# IMU_Schematics.net
KiCad netlist of a schematic drawn in Altium Designer
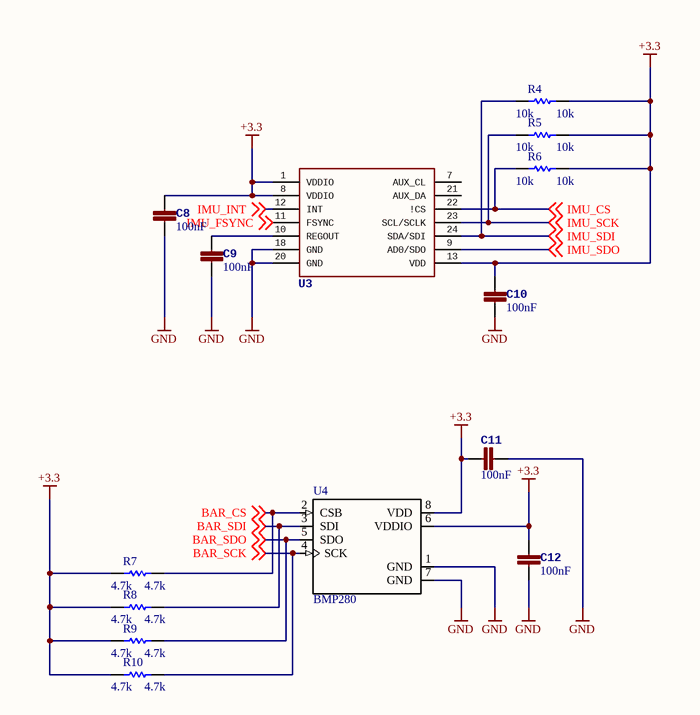
[diagram p0: IMU_Schematics.SchDoc]

(export (version "E")
  (design (tool "Eeschema 10.0.6"))
  (components
    (comp (ref "C8")
      (value "100nF")
      (footprint "_0603")
      (fields (field (name "Comment") "Cap"))
      (libsource (lib "Passives_Integrated_Library") (part "Cap_1"))
    )
    (comp (ref "C9")
      (value "100nF")
      (footprint "_0603")
      (fields (field (name "Comment") "Cap"))
      (libsource (lib "Passives_Integrated_Library") (part "Cap_1"))
    )
    (comp (ref "C10")
      (value "100nF")
      (footprint "_0603")
      (fields (field (name "Comment") "Cap"))
      (libsource (lib "Passives_Integrated_Library") (part "Cap_1"))
    )
    (comp (ref "C11")
      (value "100nF")
      (footprint "_0603")
      (fields (field (name "Comment") "Cap"))
      (libsource (lib "") (part "Cap_1_1"))
    )
    (comp (ref "C12")
      (value "100nF")
      (footprint "_0603")
      (fields (field (name "Comment") "Cap"))
      (libsource (lib "") (part "Cap_1_2"))
    )
    (comp (ref "R4")
      (value "10k")
      (footprint "RES0603")
      (description "TOTAL SMD RESISTOR PACK")
      (fields (field (name "ALTIUM_VALUE") "10k") (field (name "DESIGNER") "Abbas Basereh"))
      (libsource (lib "Passives_Integrated_Library") (part "RES SMD PACKAGE"))
    )
    (comp (ref "R5")
      (value "10k")
      (footprint "RES0603")
      (description "TOTAL SMD RESISTOR PACK")
      (fields (field (name "ALTIUM_VALUE") "10k") (field (name "DESIGNER") "Abbas Basereh"))
      (libsource (lib "Passives_Integrated_Library") (part "RES SMD PACKAGE"))
    )
    (comp (ref "R6")
      (value "10k")
      (footprint "RES0603")
      (description "TOTAL SMD RESISTOR PACK")
      (fields (field (name "ALTIUM_VALUE") "10k") (field (name "DESIGNER") "Abbas Basereh"))
      (libsource (lib "Passives_Integrated_Library") (part "RES SMD PACKAGE"))
    )
    (comp (ref "R7")
      (value "4.7k")
      (footprint "RES0603")
      (description "TOTAL SMD RESISTOR PACK")
      (fields (field (name "ALTIUM_VALUE") "4.7k") (field (name "DESIGNER") "Abbas Basereh"))
      (libsource (lib "Passives_Integrated_Library") (part "RES SMD PACKAGE"))
    )
    (comp (ref "R8")
      (value "4.7k")
      (footprint "RES0603")
      (description "TOTAL SMD RESISTOR PACK")
      (fields (field (name "ALTIUM_VALUE") "4.7k") (field (name "DESIGNER") "Abbas Basereh"))
      (libsource (lib "Passives_Integrated_Library") (part "RES SMD PACKAGE"))
    )
    (comp (ref "R9")
      (value "4.7k")
      (footprint "RES0603")
      (description "TOTAL SMD RESISTOR PACK")
      (fields (field (name "ALTIUM_VALUE") "4.7k") (field (name "DESIGNER") "Abbas Basereh"))
      (libsource (lib "Passives_Integrated_Library") (part "RES SMD PACKAGE"))
    )
    (comp (ref "R10")
      (value "4.7k")
      (footprint "RES0603")
      (description "TOTAL SMD RESISTOR PACK")
      (fields (field (name "ALTIUM_VALUE") "4.7k") (field (name "DESIGNER") "Abbas Basereh"))
      (libsource (lib "Passives_Integrated_Library") (part "RES SMD PACKAGE"))
    )
    (comp (ref "U3")
      (value "MPU-9250")
      (footprint "_QFN-24-EP")
      (libsource (lib "Sensors_Integrated_Library") (part "MPU-9250"))
    )
    (comp (ref "U4")
      (value "BMP280")
      (footprint "*XDCR_BMP280")
      (description "BMP280 Absolute Barometric Pressure Sensor for Battery Powered Devices 2 x 2.5mm")
      (fields (field (name "MF") "Bosch"))
      (libsource (lib "BMP280") (part "BMP280"))
    )
  )
  (nets
    (net (code "1") (name "+3.3") (class "Default")
      (node (ref "C10") (pin "2") (pinfunction "2_2") (pintype "passive"))
      (node (ref "C11") (pin "1") (pinfunction "1_1") (pintype "passive"))
      (node (ref "C12") (pin "1") (pinfunction "1_1") (pintype "passive"))
      (node (ref "C8") (pin "2") (pinfunction "2_2") (pintype "passive"))
      (node (ref "R10") (pin "1") (pinfunction "1_1") (pintype "passive"))
      (node (ref "R4") (pin "2") (pinfunction "2_2") (pintype "passive"))
      (node (ref "R5") (pin "2") (pinfunction "2_2") (pintype "passive"))
      (node (ref "R6") (pin "2") (pinfunction "2_2") (pintype "passive"))
      (node (ref "R7") (pin "1") (pinfunction "1_1") (pintype "passive"))
      (node (ref "R8") (pin "1") (pinfunction "1_1") (pintype "passive"))
      (node (ref "R9") (pin "1") (pinfunction "1_1") (pintype "passive"))
      (node (ref "U3") (pin "1") (pinfunction "VDDIO_1") (pintype "passive"))
      (node (ref "U3") (pin "13") (pinfunction "VDD_13") (pintype "passive"))
      (node (ref "U3") (pin "8") (pinfunction "VDDIO_8") (pintype "passive"))
      (node (ref "U4") (pin "6") (pinfunction "VDDIO_6") (pintype "power_in"))
      (node (ref "U4") (pin "8") (pinfunction "VDD_8") (pintype "power_in"))
    )
    (net (code "2") (name "BAR_CS") (class "Default")
      (node (ref "R7") (pin "2") (pinfunction "2_2") (pintype "passive"))
      (node (ref "U4") (pin "2") (pinfunction "CSB_2") (pintype "input"))
    )
    (net (code "3") (name "BAR_SCK") (class "Default")
      (node (ref "R10") (pin "2") (pinfunction "2_2") (pintype "passive"))
      (node (ref "U4") (pin "4") (pinfunction "SCK_4") (pintype "input"))
    )
    (net (code "4") (name "BAR_SDI") (class "Default")
      (node (ref "R8") (pin "2") (pinfunction "2_2") (pintype "passive"))
      (node (ref "U4") (pin "3") (pinfunction "SDI_3") (pintype "bidirectional"))
    )
    (net (code "5") (name "BAR_SDO") (class "Default")
      (node (ref "R9") (pin "2") (pinfunction "2_2") (pintype "passive"))
      (node (ref "U4") (pin "5") (pinfunction "SDO_5") (pintype "bidirectional"))
    )
    (net (code "6") (name "GND") (class "Default")
      (node (ref "C10") (pin "1") (pinfunction "1_1") (pintype "passive"))
      (node (ref "C11") (pin "2") (pinfunction "2_2") (pintype "passive"))
      (node (ref "C12") (pin "2") (pinfunction "2_2") (pintype "passive"))
      (node (ref "C8") (pin "1") (pinfunction "1_1") (pintype "passive"))
      (node (ref "C9") (pin "1") (pinfunction "1_1") (pintype "passive"))
      (node (ref "U3") (pin "18") (pinfunction "GND_18") (pintype "passive"))
      (node (ref "U3") (pin "20") (pinfunction "GND_20") (pintype "passive"))
      (node (ref "U4") (pin "1") (pinfunction "GND_1") (pintype "power_in"))
      (node (ref "U4") (pin "7") (pinfunction "GND_7") (pintype "power_in"))
    )
    (net (code "7") (name "IMU_CS") (class "Default")
      (node (ref "R6") (pin "1") (pinfunction "1_1") (pintype "passive"))
      (node (ref "U3") (pin "22") (pinfunction "!CS_22") (pintype "passive"))
    )
    (net (code "8") (name "IMU_FSYNC") (class "Default")
      (node (ref "U3") (pin "11") (pinfunction "FSYNC_11") (pintype "passive"))
    )
    (net (code "9") (name "IMU_INT") (class "Default")
      (node (ref "U3") (pin "12") (pinfunction "INT_12") (pintype "passive"))
    )
    (net (code "10") (name "IMU_SCK") (class "Default")
      (node (ref "R5") (pin "1") (pinfunction "1_1") (pintype "passive"))
      (node (ref "U3") (pin "23") (pinfunction "SCL/SCLK_23") (pintype "passive"))
    )
    (net (code "11") (name "IMU_SDI") (class "Default")
      (node (ref "R4") (pin "1") (pinfunction "1_1") (pintype "passive"))
      (node (ref "U3") (pin "24") (pinfunction "SDA/SDI_24") (pintype "passive"))
    )
    (net (code "12") (name "IMU_SDO") (class "Default")
      (node (ref "U3") (pin "9") (pinfunction "AD0/SDO_9") (pintype "passive"))
    )
    (net (code "13") (name "Net-(U3-REGOUT)") (class "Default")
      (node (ref "C9") (pin "2") (pinfunction "2_2") (pintype "passive"))
      (node (ref "U3") (pin "10") (pinfunction "REGOUT_10") (pintype "passive"))
    )
    (net (code "14") (name "unconnected-(U3-AUX_CL-Pad7)") (class "Default")
      (node (ref "U3") (pin "7") (pinfunction "AUX_CL_7") (pintype "passive"))
    )
    (net (code "15") (name "unconnected-(U3-AUX_DA-Pad21)") (class "Default")
      (node (ref "U3") (pin "21") (pinfunction "AUX_DA_21") (pintype "passive"))
    )
  )
)
